# Quat.net
KiCad netlist of a schematic drawn in Altium Designer
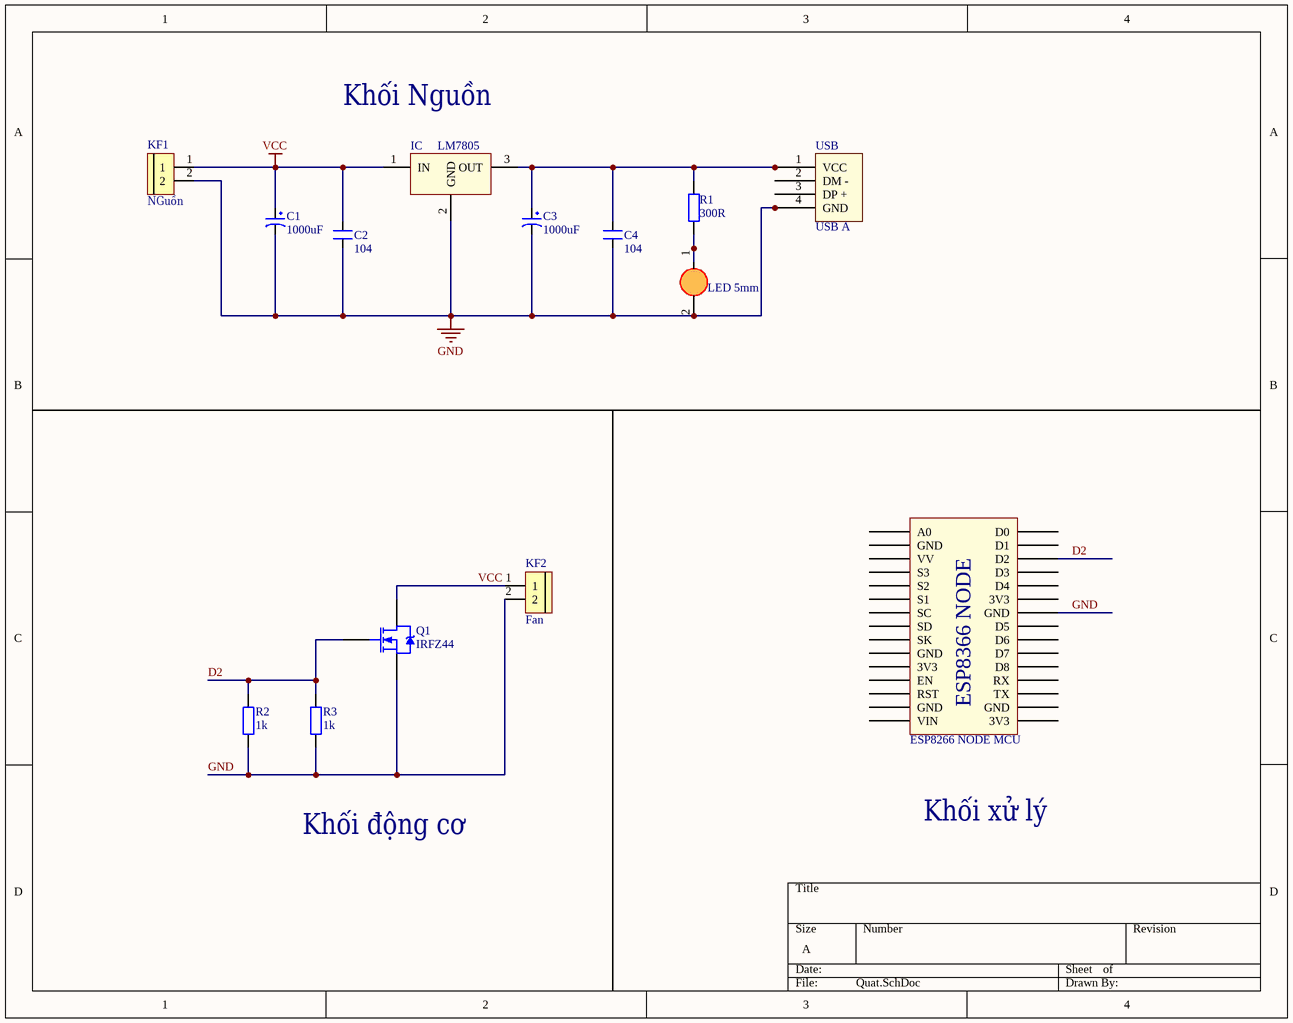
[diagram p0: Quat.SchDoc]

(export (version "E")
  (design (tool "Eeschema 10.0.6"))
  (components
    (comp (ref "*")
      (value "ESP8266 NODE MCU")
      (footprint "ESP8266 NODE MCU")
      (libsource (lib "Module") (part "ESP8266 NODE MCU"))
    )
    (comp (ref "C1")
      (value "1000uF")
      (footprint "CAP secmi case A")
      (libsource (lib "my Library") (part "tu secmi"))
    )
    (comp (ref "C2")
      (value "104")
      (footprint "CN2")
      (description "Cap np 104 => 105pF")
      (libsource (lib "my Library") (part "CN2"))
    )
    (comp (ref "C3")
      (value "1000uF")
      (footprint "CAP secmi case A")
      (libsource (lib "my Library") (part "tu secmi"))
    )
    (comp (ref "C4")
      (value "104")
      (footprint "CN2")
      (description "Cap np 104 => 105pF")
      (libsource (lib "my Library") (part "CN2"))
    )
    (comp (ref "IC")
      (value "LM7805")
      (footprint "QTO-220")
      (description "On ap +, from + 5 to + 24VDC")
      (libsource (lib "Cty1") (part "LM78xx"))
    )
    (comp (ref "KF1")
      (value "NGuồn")
      (footprint "Con 2 KF301 5.08")
      (description "Cắm")
      (libsource (lib "") (part "CON 2 KF301_1"))
    )
    (comp (ref "KF2")
      (value "Fan")
      (footprint "Con 2 KF301 5.08")
      (description "Cắm")
      (libsource (lib "Connector") (part "CON 2 KF301"))
    )
    (comp (ref "LED1") (value "LED 5mm") (footprint "LED5MM") (libsource (lib "my Library") (part "LED 5mm")))
    (comp (ref "Q1")
      (value "IRFZ44")
      (footprint "TO220")
      (description "TO-220")
      (libsource (lib "TranFet") (part "FET IRFZ44 DIP"))
    )
    (comp (ref "R1")
      (value "300R")
      (footprint "DIEN TRO 1/4 W")
      (description "Resistor")
      (fields (field (name "Comment") "R0.4W") (field (name "PUBLISHER") "Altium Limited"))
      (libsource (lib "my Library") (part "Res 1/4 W"))
    )
    (comp (ref "R2")
      (value "1k")
      (footprint "tro vach 1/2w")
      (description "Cắm")
      (libsource (lib "Resistor") (part "Tro Vach 1/2W 5% 1k"))
    )
    (comp (ref "R3")
      (value "1k")
      (footprint "tro vach 1/2w")
      (description "Cắm")
      (libsource (lib "Resistor") (part "Tro Vach 1/2W 5% 1k"))
    )
    (comp (ref "USB")
      (value "USB A")
      (footprint "USB A CN DIP")
      (description "USB Type A")
      (libsource (lib "Component") (part "USB A CN DIP"))
    )
  )
  (nets
    (net (code "1") (name "/D2") (class "Default")
      (node (ref "*") (pin "28") (pinfunction "D2_28") (pintype "passive"))
      (node (ref "Q1") (pin "1") (pinfunction "G_1") (pintype "passive"))
      (node (ref "R2") (pin "1") (pinfunction "1_1") (pintype "passive"))
      (node (ref "R3") (pin "1") (pinfunction "1_1") (pintype "passive"))
    )
    (net (code "2") (name "GND") (class "Default")
      (node (ref "*") (pin "24") (pinfunction "GND_24") (pintype "passive"))
      (node (ref "C1") (pin "2") (pinfunction "2_2") (pintype "passive"))
      (node (ref "C2") (pin "2") (pinfunction "2_2") (pintype "passive"))
      (node (ref "C3") (pin "2") (pinfunction "2_2") (pintype "passive"))
      (node (ref "C4") (pin "2") (pinfunction "2_2") (pintype "passive"))
      (node (ref "IC") (pin "2") (pinfunction "GND_2") (pintype "passive"))
      (node (ref "KF1") (pin "2") (pinfunction "2_2") (pintype "passive"))
      (node (ref "KF2") (pin "2") (pinfunction "2_2") (pintype "passive"))
      (node (ref "LED1") (pin "2") (pinfunction "K_2") (pintype "passive"))
      (node (ref "Q1") (pin "3") (pinfunction "S_3") (pintype "passive"))
      (node (ref "R2") (pin "2") (pinfunction "2_2") (pintype "passive"))
      (node (ref "R3") (pin "2") (pinfunction "2_2") (pintype "passive"))
      (node (ref "USB") (pin "4") (pinfunction "GND_4") (pintype "passive"))
    )
    (net (code "3") (name "Net-(IC-OUT)") (class "Default")
      (node (ref "C3") (pin "1") (pinfunction "1_1") (pintype "passive"))
      (node (ref "C4") (pin "1") (pinfunction "1_1") (pintype "passive"))
      (node (ref "IC") (pin "3") (pinfunction "OUT_3") (pintype "passive"))
      (node (ref "R1") (pin "1") (pinfunction "1_1") (pintype "passive"))
      (node (ref "USB") (pin "1") (pinfunction "VCC_1") (pintype "passive"))
    )
    (net (code "4") (name "Net-(LED1-A)") (class "Default")
      (node (ref "LED1") (pin "1") (pinfunction "A_1") (pintype "passive"))
      (node (ref "R1") (pin "2") (pinfunction "2_2") (pintype "passive"))
    )
    (net (code "5") (name "VCC") (class "Default")
      (node (ref "C1") (pin "1") (pinfunction "1_1") (pintype "passive"))
      (node (ref "C2") (pin "1") (pinfunction "1_1") (pintype "passive"))
      (node (ref "IC") (pin "1") (pinfunction "IN_1") (pintype "passive"))
      (node (ref "KF1") (pin "1") (pinfunction "1_1") (pintype "passive"))
      (node (ref "KF2") (pin "1") (pinfunction "1_1") (pintype "passive"))
      (node (ref "Q1") (pin "2") (pinfunction "D_2") (pintype "passive"))
    )
    (net (code "6") (name "unconnected-(*-3V3-Pad11)") (class "Default")
      (node (ref "*") (pin "11") (pinfunction "3V3_11") (pintype "passive"))
    )
    (net (code "7") (name "unconnected-(*-3V3-Pad16)") (class "Default")
      (node (ref "*") (pin "16") (pinfunction "3V3_16") (pintype "passive"))
    )
    (net (code "8") (name "unconnected-(*-3V3-Pad25)") (class "Default")
      (node (ref "*") (pin "25") (pinfunction "3V3_25") (pintype "passive"))
    )
    (net (code "9") (name "unconnected-(*-A0-Pad1)") (class "Default")
      (node (ref "*") (pin "1") (pinfunction "A0_1") (pintype "passive"))
    )
    (net (code "10") (name "unconnected-(*-D0-Pad30)") (class "Default")
      (node (ref "*") (pin "30") (pinfunction "D0_30") (pintype "passive"))
    )
    (net (code "11") (name "unconnected-(*-D1-Pad29)") (class "Default")
      (node (ref "*") (pin "29") (pinfunction "D1_29") (pintype "passive"))
    )
    (net (code "12") (name "unconnected-(*-D3-Pad27)") (class "Default")
      (node (ref "*") (pin "27") (pinfunction "D3_27") (pintype "passive"))
    )
    (net (code "13") (name "unconnected-(*-D4-Pad26)") (class "Default")
      (node (ref "*") (pin "26") (pinfunction "D4_26") (pintype "passive"))
    )
    (net (code "14") (name "unconnected-(*-D5-Pad23)") (class "Default")
      (node (ref "*") (pin "23") (pinfunction "D5_23") (pintype "passive"))
    )
    (net (code "15") (name "unconnected-(*-D6-Pad22)") (class "Default")
      (node (ref "*") (pin "22") (pinfunction "D6_22") (pintype "passive"))
    )
    (net (code "16") (name "unconnected-(*-D7-Pad21)") (class "Default")
      (node (ref "*") (pin "21") (pinfunction "D7_21") (pintype "passive"))
    )
    (net (code "17") (name "unconnected-(*-D8-Pad20)") (class "Default")
      (node (ref "*") (pin "20") (pinfunction "D8_20") (pintype "passive"))
    )
    (net (code "18") (name "unconnected-(*-EN-Pad12)") (class "Default")
      (node (ref "*") (pin "12") (pinfunction "EN_12") (pintype "passive"))
    )
    (net (code "19") (name "unconnected-(*-GND-Pad2)") (class "Default")
      (node (ref "*") (pin "2") (pinfunction "GND_2") (pintype "passive"))
    )
    (net (code "20") (name "unconnected-(*-GND-Pad10)") (class "Default")
      (node (ref "*") (pin "10") (pinfunction "GND_10") (pintype "passive"))
    )
    (net (code "21") (name "unconnected-(*-GND-Pad14)") (class "Default")
      (node (ref "*") (pin "14") (pinfunction "GND_14") (pintype "passive"))
    )
    (net (code "22") (name "unconnected-(*-GND-Pad17)") (class "Default")
      (node (ref "*") (pin "17") (pinfunction "GND_17") (pintype "passive"))
    )
    (net (code "23") (name "unconnected-(*-RST-Pad13)") (class "Default")
      (node (ref "*") (pin "13") (pinfunction "RST_13") (pintype "passive"))
    )
    (net (code "24") (name "unconnected-(*-RX-Pad19)") (class "Default")
      (node (ref "*") (pin "19") (pinfunction "RX_19") (pintype "passive"))
    )
    (net (code "25") (name "unconnected-(*-S1-Pad6)") (class "Default")
      (node (ref "*") (pin "6") (pinfunction "S1_6") (pintype "passive"))
    )
    (net (code "26") (name "unconnected-(*-S2-Pad5)") (class "Default")
      (node (ref "*") (pin "5") (pinfunction "S2_5") (pintype "passive"))
    )
    (net (code "27") (name "unconnected-(*-S3-Pad4)") (class "Default")
      (node (ref "*") (pin "4") (pinfunction "S3_4") (pintype "passive"))
    )
    (net (code "28") (name "unconnected-(*-SC-Pad7)") (class "Default")
      (node (ref "*") (pin "7") (pinfunction "SC_7") (pintype "passive"))
    )
    (net (code "29") (name "unconnected-(*-SD-Pad8)") (class "Default")
      (node (ref "*") (pin "8") (pinfunction "SD_8") (pintype "passive"))
    )
    (net (code "30") (name "unconnected-(*-SK-Pad9)") (class "Default")
      (node (ref "*") (pin "9") (pinfunction "SK_9") (pintype "passive"))
    )
    (net (code "31") (name "unconnected-(*-TX-Pad18)") (class "Default")
      (node (ref "*") (pin "18") (pinfunction "TX_18") (pintype "passive"))
    )
    (net (code "32") (name "unconnected-(*-VIN-Pad15)") (class "Default")
      (node (ref "*") (pin "15") (pinfunction "VIN_15") (pintype "passive"))
    )
    (net (code "33") (name "unconnected-(*-VV-Pad3)") (class "Default")
      (node (ref "*") (pin "3") (pinfunction "VV_3") (pintype "passive"))
    )
    (net (code "34") (name "unconnected-(USB-DM_--Pad2)") (class "Default")
      (node (ref "USB") (pin "2") (pinfunction "DM_-_2") (pintype "passive"))
    )
    (net (code "35") (name "unconnected-(USB-DP_+-Pad3)") (class "Default")
      (node (ref "USB") (pin "3") (pinfunction "DP_+_3") (pintype "passive"))
    )
  )
)
